# Perco_KT02_3.net
KiCad netlist of a schematic drawn in Altium Designer
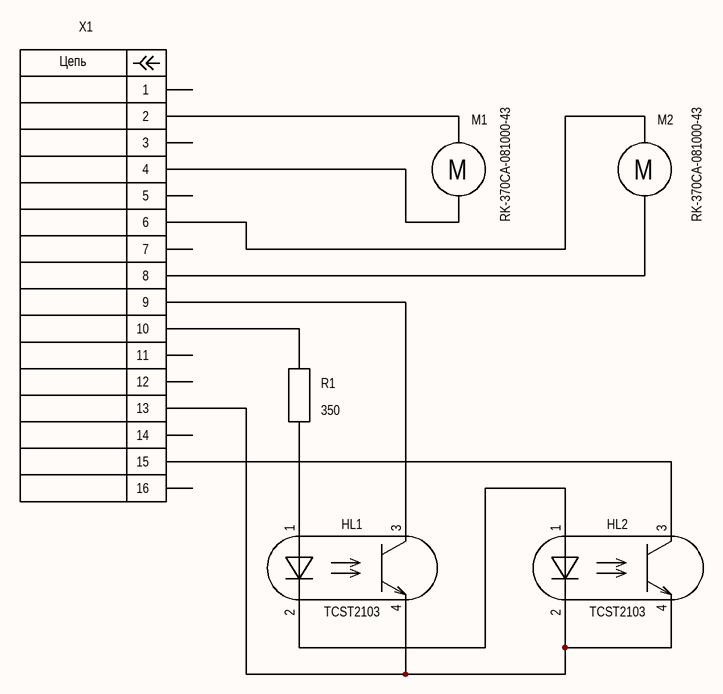
[diagram p0: Perco KT02.3.SchDoc]

(export (version "E")
  (design (tool "Eeschema 10.0.6"))
  (components
    (comp (ref "HL1")
      (value "TCST2103")
      (footprint "214A67")
      (description "Photointerrupter Barrier")
      (fields (field (name "MANUFACTURER") "Fairchild Semiconductor"))
      (libsource (lib "Sensors Optical") (part "TCST2103"))
    )
    (comp (ref "HL2")
      (value "TCST2103")
      (footprint "214A67")
      (description "Photointerrupter Barrier")
      (fields (field (name "MANUFACTURER") "Fairchild Semiconductor"))
      (libsource (lib "Sensors Optical") (part "TCST2103"))
    )
    (comp (ref "M1")
      (value "RK-370CA-081000-43")
      (description "Default")
      (libsource (lib "Power Motor drivers") (part "Default_1"))
    )
    (comp (ref "M2")
      (value "RK-370CA-081000-43")
      (description "Default")
      (libsource (lib "Power Motor drivers") (part "Default_1"))
    )
    (comp (ref "R1")
      (value "350")
      (footprint "RESC1608N")
      (description "RESC 330 0603(1608)")
      (fields (field (name "MANUFACTURER") "Yageo") (field (name "TOLERANCE") "±5%"))
      (libsource (lib "Resistors Ceramic SMD 1608") (part "RC0603JR-07330RL"))
    )
    (comp (ref "X1")
      (value "302-S161")
      (footprint "IDC-16/2N")
      (description "Connector Rectangular IDC M 16P 2R 2.54")
      (fields (field (name "MANUFACTURER") "On Shore Technology"))
      (libsource (lib "Connectors Rectangular") (part "302-S161"))
    )
  )
  (nets
    (net (code "1") (name "Net-(HL1-Anode)") (class "Default")
      (node (ref "HL1") (pin "1") (pinfunction "Anode_1") (pintype "passive"))
      (node (ref "R1") (pin "2") (pinfunction "2_2") (pintype "passive"))
    )
    (net (code "2") (name "Net-(HL1-Cathode)") (class "Default")
      (node (ref "HL1") (pin "2") (pinfunction "Cathode_2") (pintype "passive"))
      (node (ref "HL2") (pin "1") (pinfunction "Anode_1") (pintype "passive"))
    )
    (net (code "3") (name "Net-(HL1-Collector)") (class "Default")
      (node (ref "HL1") (pin "3") (pinfunction "Collector_3") (pintype "passive"))
      (node (ref "X1") (pin "9") (pinfunction "9_9") (pintype "passive"))
    )
    (net (code "4") (name "Net-(HL1-Emitter)") (class "Default")
      (node (ref "HL1") (pin "4") (pinfunction "Emitter_4") (pintype "passive"))
      (node (ref "HL2") (pin "2") (pinfunction "Cathode_2") (pintype "passive"))
      (node (ref "HL2") (pin "4") (pinfunction "Emitter_4") (pintype "passive"))
      (node (ref "X1") (pin "13") (pinfunction "13_13") (pintype "passive"))
    )
    (net (code "5") (name "Net-(HL2-Collector)") (class "Default")
      (node (ref "HL2") (pin "3") (pinfunction "Collector_3") (pintype "passive"))
      (node (ref "X1") (pin "15") (pinfunction "15_15") (pintype "passive"))
    )
    (net (code "6") (name "Net-(M1-Pad1)") (class "Default")
      (node (ref "M1") (pin "1") (pintype "passive"))
      (node (ref "X1") (pin "2") (pinfunction "2_2") (pintype "passive"))
    )
    (net (code "7") (name "Net-(M1-Pad2)") (class "Default")
      (node (ref "M1") (pin "2") (pintype "passive"))
      (node (ref "X1") (pin "4") (pinfunction "4_4") (pintype "passive"))
    )
    (net (code "8") (name "Net-(M2-Pad1)") (class "Default")
      (node (ref "M2") (pin "1") (pintype "passive"))
      (node (ref "X1") (pin "6") (pinfunction "6_6") (pintype "passive"))
    )
    (net (code "9") (name "Net-(M2-Pad2)") (class "Default")
      (node (ref "M2") (pin "2") (pintype "passive"))
      (node (ref "X1") (pin "8") (pinfunction "8_8") (pintype "passive"))
    )
    (net (code "10") (name "Net-(R1-Pad1)") (class "Default")
      (node (ref "R1") (pin "1") (pinfunction "1_1") (pintype "passive"))
      (node (ref "X1") (pin "10") (pinfunction "10_10") (pintype "passive"))
    )
    (net (code "11") (name "unconnected-(X1-Pad1)") (class "Default")
      (node (ref "X1") (pin "1") (pinfunction "1_1") (pintype "passive"))
    )
    (net (code "12") (name "unconnected-(X1-Pad3)") (class "Default")
      (node (ref "X1") (pin "3") (pinfunction "3_3") (pintype "passive"))
    )
    (net (code "13") (name "unconnected-(X1-Pad5)") (class "Default")
      (node (ref "X1") (pin "5") (pinfunction "5_5") (pintype "passive"))
    )
    (net (code "14") (name "unconnected-(X1-Pad7)") (class "Default")
      (node (ref "X1") (pin "7") (pinfunction "7_7") (pintype "passive"))
    )
    (net (code "15") (name "unconnected-(X1-Pad11)") (class "Default")
      (node (ref "X1") (pin "11") (pinfunction "11_11") (pintype "passive"))
    )
    (net (code "16") (name "unconnected-(X1-Pad12)") (class "Default")
      (node (ref "X1") (pin "12") (pinfunction "12_12") (pintype "passive"))
    )
    (net (code "17") (name "unconnected-(X1-Pad14)") (class "Default")
      (node (ref "X1") (pin "14") (pinfunction "14_14") (pintype "passive"))
    )
    (net (code "18") (name "unconnected-(X1-Pad16)") (class "Default")
      (node (ref "X1") (pin "16") (pinfunction "16_16") (pintype "passive"))
    )
  )
)
